# SW.net
KiCad netlist of a schematic drawn in Altium Designer
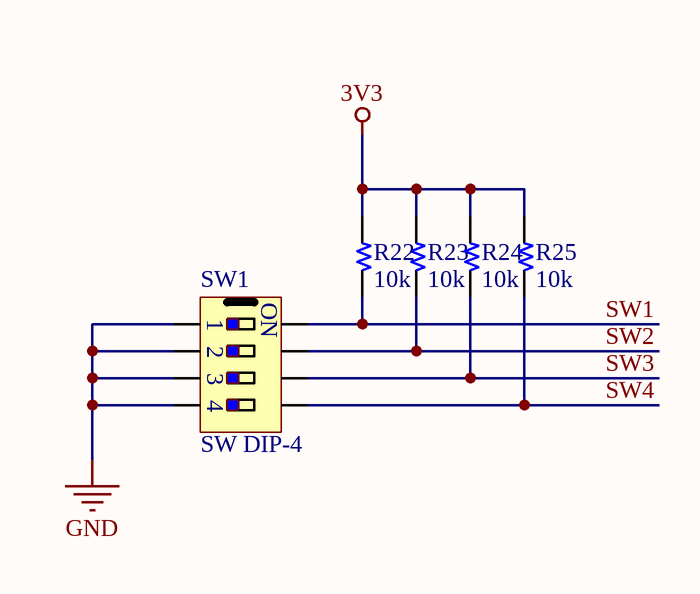
[diagram p0: SW.SchDoc]

(export (version "E")
  (design (tool "Eeschema 10.0.6"))
  (components
    (comp (ref "R22")
      (value "10k")
      (footprint "R 0603")
      (description "Resistor")
      (libsource (lib "chipfc_libs") (part "Resistor"))
    )
    (comp (ref "R23")
      (value "10k")
      (footprint "R 0603")
      (description "Resistor")
      (libsource (lib "chipfc_libs") (part "Resistor"))
    )
    (comp (ref "R24")
      (value "10k")
      (footprint "R 0603")
      (description "Resistor")
      (libsource (lib "chipfc_libs") (part "Resistor"))
    )
    (comp (ref "R25")
      (value "10k")
      (footprint "R 0603")
      (description "Resistor")
      (libsource (lib "chipfc_libs") (part "Resistor"))
    )
    (comp (ref "SW1")
      (value "SW DIP-4")
      (footprint "SW/DIP4")
      (libsource (lib "chipfc_libs") (part "SW DIP-4"))
    )
  )
  (nets
    (net (code "1") (name "/SW1") (class "Default")
      (node (ref "R22") (pin "1") (pinfunction "1_1") (pintype "passive"))
      (node (ref "SW1") (pin "8") (pinfunction "8_8") (pintype "passive"))
    )
    (net (code "2") (name "/SW2") (class "Default")
      (node (ref "R23") (pin "1") (pinfunction "1_1") (pintype "passive"))
      (node (ref "SW1") (pin "7") (pinfunction "7_7") (pintype "passive"))
    )
    (net (code "3") (name "/SW3") (class "Default")
      (node (ref "R24") (pin "1") (pinfunction "1_1") (pintype "passive"))
      (node (ref "SW1") (pin "6") (pinfunction "6_6") (pintype "passive"))
    )
    (net (code "4") (name "/SW4") (class "Default")
      (node (ref "R25") (pin "1") (pinfunction "1_1") (pintype "passive"))
      (node (ref "SW1") (pin "5") (pinfunction "5_5") (pintype "passive"))
    )
    (net (code "5") (name "3V3") (class "Default")
      (node (ref "R22") (pin "2") (pinfunction "2_2") (pintype "passive"))
      (node (ref "R23") (pin "2") (pinfunction "2_2") (pintype "passive"))
      (node (ref "R24") (pin "2") (pinfunction "2_2") (pintype "passive"))
      (node (ref "R25") (pin "2") (pinfunction "2_2") (pintype "passive"))
    )
    (net (code "6") (name "GND") (class "Default")
      (node (ref "SW1") (pin "1") (pinfunction "1_1") (pintype "passive"))
      (node (ref "SW1") (pin "2") (pinfunction "2_2") (pintype "passive"))
      (node (ref "SW1") (pin "3") (pinfunction "3_3") (pintype "passive"))
      (node (ref "SW1") (pin "4") (pinfunction "4_4") (pintype "passive"))
    )
  )
)
